# schematic.net
KiCad netlist of a schematic drawn in EAGLE
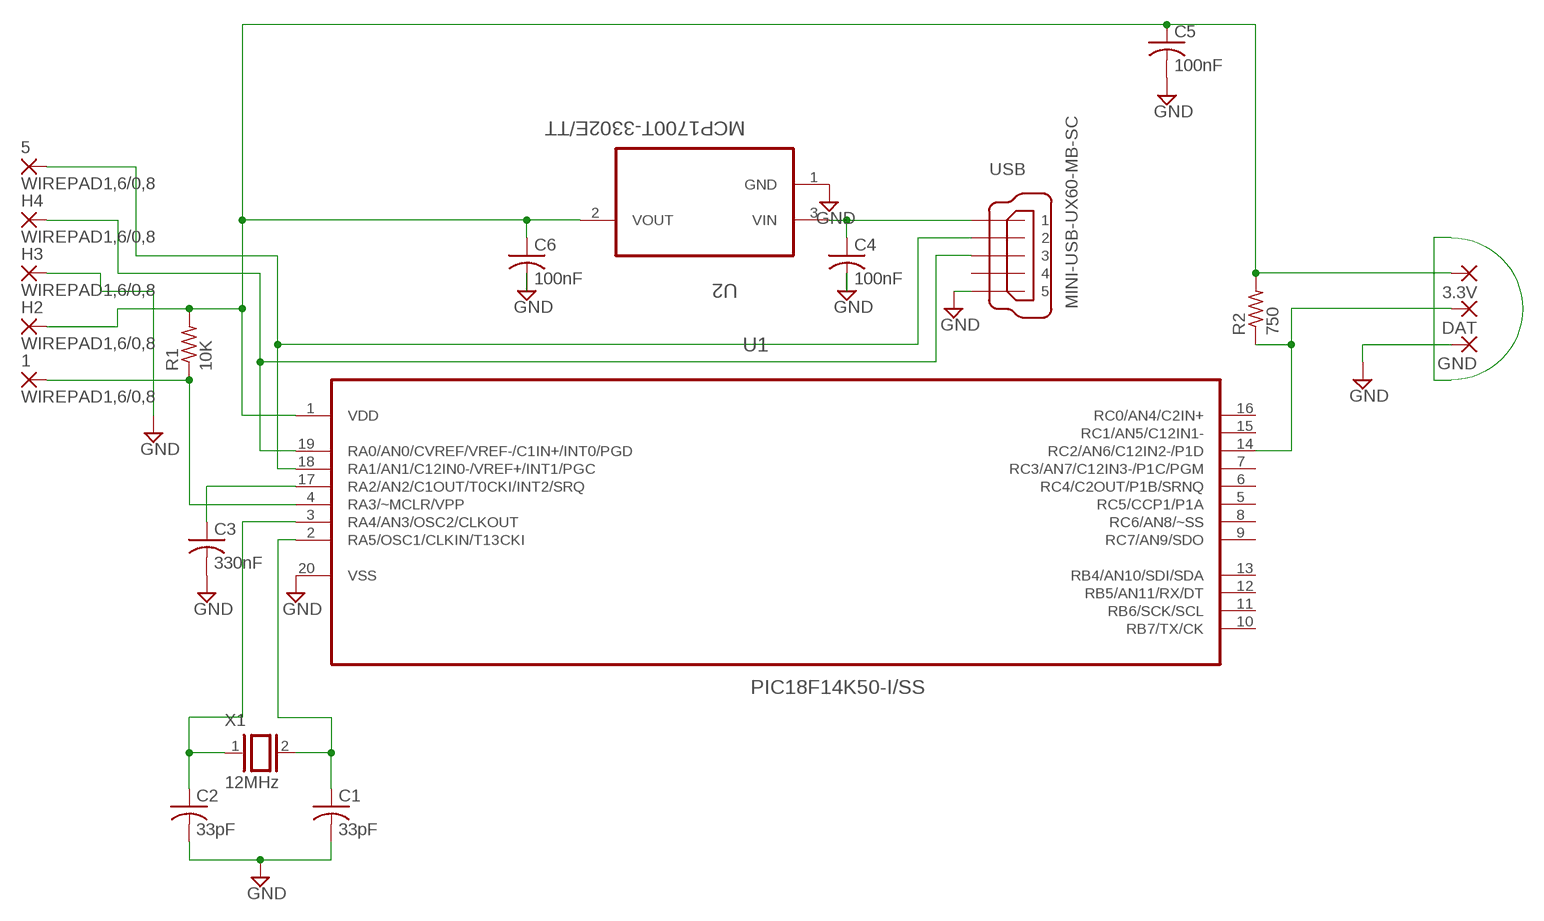
[diagram p0: schematic, sheet 1]

(export (version "E")
  (design (tool "Eeschema 10.0.6"))
  (components
    (comp (ref "1")
      (value "WIREPAD1,6/0,8")
      (footprint "eagle-import:1,6_0,8")
      (libsource (lib "eagle-import") (part "WIREPAD1,6/0,8"))
    )
    (comp (ref "3.3V")
      (value "SMD2")
      (footprint "eagle-import:SMD1,27-2,54")
      (libsource (lib "eagle-import") (part "SMD2"))
    )
    (comp (ref "5")
      (value "WIREPAD1,6/0,8")
      (footprint "eagle-import:1,6_0,8")
      (libsource (lib "eagle-import") (part "WIREPAD1,6/0,8"))
    )
    (comp (ref "C1")
      (value "33pF")
      (footprint "eagle-import:C0402")
      (libsource (lib "eagle-import") (part "C-USC0402"))
    )
    (comp (ref "C2")
      (value "33pF")
      (footprint "eagle-import:C0402")
      (libsource (lib "eagle-import") (part "C-USC0402"))
    )
    (comp (ref "C3")
      (value "330nF")
      (footprint "eagle-import:C0603")
      (libsource (lib "eagle-import") (part "C-USC0603"))
    )
    (comp (ref "C4")
      (value "100nF")
      (footprint "eagle-import:C0402")
      (libsource (lib "eagle-import") (part "C-USC0402"))
    )
    (comp (ref "C5")
      (value "100nF")
      (footprint "eagle-import:C0402")
      (libsource (lib "eagle-import") (part "C-USC0402"))
    )
    (comp (ref "C6")
      (value "100nF")
      (footprint "eagle-import:C0402")
      (libsource (lib "eagle-import") (part "C-USC0402"))
    )
    (comp (ref "DAT")
      (value "SMD2")
      (footprint "eagle-import:SMD1,27-2,54")
      (libsource (lib "eagle-import") (part "SMD2"))
    )
    (comp (ref "GND")
      (value "SMD2")
      (footprint "eagle-import:SMD1,27-2,54")
      (libsource (lib "eagle-import") (part "SMD2"))
    )
    (comp (ref "H2")
      (value "WIREPAD1,6/0,8")
      (footprint "eagle-import:1,6_0,8")
      (libsource (lib "eagle-import") (part "WIREPAD1,6/0,8"))
    )
    (comp (ref "H3")
      (value "WIREPAD1,6/0,8")
      (footprint "eagle-import:1,6_0,8")
      (libsource (lib "eagle-import") (part "WIREPAD1,6/0,8"))
    )
    (comp (ref "H4")
      (value "WIREPAD1,6/0,8")
      (footprint "eagle-import:1,6_0,8")
      (libsource (lib "eagle-import") (part "WIREPAD1,6/0,8"))
    )
    (comp (ref "R1")
      (value "10K")
      (footprint "eagle-import:R0805")
      (libsource (lib "eagle-import") (part "R-US_R0805"))
    )
    (comp (ref "R2")
      (value "750")
      (footprint "eagle-import:R0805")
      (libsource (lib "eagle-import") (part "R-US_R0805"))
    )
    (comp (ref "U1")
      (value "PIC18F14K50-I/SS")
      (footprint "eagle-import:SOP65P780X200-20N")
      (libsource (lib "eagle-import") (part "PIC18F14K50-I/SS"))
    )
    (comp (ref "U2")
      (value "MCP1700T-3302E/TT")
      (footprint "eagle-import:SOT95P237X112-3N")
      (libsource (lib "eagle-import") (part "MCP1700T-3302E/TT"))
    )
    (comp (ref "USB")
      (value "MINI-USB-UX60-MB-SC")
      (footprint "eagle-import:UX60-MB-SC")
      (libsource (lib "eagle-import") (part "MINI-USB-UX60-MB-SC"))
    )
    (comp (ref "X1")
      (value "12MHz")
      (footprint "eagle-import:QS")
      (libsource (lib "eagle-import") (part "XTAL/S"))
    )
  )
  (nets
    (net (code "1") (name "GND") (class "Default")
      (node (ref "C1") (pin "2") (pinfunction "2_2") (pintype "passive"))
      (node (ref "C2") (pin "2") (pinfunction "2_2") (pintype "passive"))
      (node (ref "C3") (pin "2") (pinfunction "2_2") (pintype "passive"))
      (node (ref "C4") (pin "2") (pinfunction "2_2") (pintype "passive"))
      (node (ref "C5") (pin "2") (pinfunction "2_2") (pintype "passive"))
      (node (ref "C6") (pin "2") (pinfunction "2_2") (pintype "passive"))
      (node (ref "GND") (pin "1") (pinfunction "P_1") (pintype "passive"))
      (node (ref "H3") (pin "1") (pinfunction "P_1") (pintype "passive"))
      (node (ref "U1") (pin "20") (pinfunction "VSS_20") (pintype "power_in"))
      (node (ref "U2") (pin "1") (pinfunction "GND_1") (pintype "passive"))
      (node (ref "USB") (pin "P$5") (pinfunction "5_P$5") (pintype "input"))
    )
    (net (code "2") (name "Net-(1-P)") (class "Default")
      (node (ref "1") (pin "1") (pinfunction "P_1") (pintype "passive"))
      (node (ref "R1") (pin "1") (pinfunction "1_1") (pintype "passive"))
      (node (ref "U1") (pin "4") (pinfunction "RA3/~{MCLR/VPP}_4") (pintype "input"))
    )
    (net (code "3") (name "Net-(3.3V-P)") (class "Default")
      (node (ref "3.3V") (pin "1") (pinfunction "P_1") (pintype "passive"))
      (node (ref "C5") (pin "1") (pinfunction "1_1") (pintype "passive"))
      (node (ref "C6") (pin "1") (pinfunction "1_1") (pintype "passive"))
      (node (ref "H2") (pin "1") (pinfunction "P_1") (pintype "passive"))
      (node (ref "R1") (pin "2") (pinfunction "2_2") (pintype "passive"))
      (node (ref "R2") (pin "2") (pinfunction "2_2") (pintype "passive"))
      (node (ref "U1") (pin "1") (pinfunction "VDD_1") (pintype "power_in"))
      (node (ref "U2") (pin "2") (pinfunction "VOUT_2") (pintype "output"))
    )
    (net (code "4") (name "Net-(5-P)") (class "Default")
      (node (ref "5") (pin "1") (pinfunction "P_1") (pintype "passive"))
      (node (ref "U1") (pin "18") (pinfunction "RA1/AN1/C12IN0-/VREF+/INT1/PGC_18") (pintype "bidirectional"))
      (node (ref "USB") (pin "P$2") (pinfunction "2_P$2") (pintype "input"))
    )
    (net (code "5") (name "Net-(DAT-P)") (class "Default")
      (node (ref "DAT") (pin "1") (pinfunction "P_1") (pintype "passive"))
      (node (ref "R2") (pin "1") (pinfunction "1_1") (pintype "passive"))
      (node (ref "U1") (pin "14") (pinfunction "RC2/AN6/C12IN2-/P1D_14") (pintype "bidirectional"))
    )
    (net (code "6") (name "Net-(H4-P)") (class "Default")
      (node (ref "H4") (pin "1") (pinfunction "P_1") (pintype "passive"))
      (node (ref "U1") (pin "19") (pinfunction "RA0/AN0/CVREF/VREF-/C1IN+/INT0/PGD_19") (pintype "bidirectional"))
      (node (ref "USB") (pin "P$3") (pinfunction "3_P$3") (pintype "input"))
    )
    (net (code "7") (name "Net-(U1-RA2{slash}AN2{slash}C1OUT{slash}T0CKI{slash}INT2{slash}SRQ)") (class "Default")
      (node (ref "C3") (pin "1") (pinfunction "1_1") (pintype "passive"))
      (node (ref "U1") (pin "17") (pinfunction "RA2/AN2/C1OUT/T0CKI/INT2/SRQ_17") (pintype "input"))
    )
    (net (code "8") (name "Net-(U1-RA4{slash}AN3{slash}OSC2{slash}CLKOUT)") (class "Default")
      (node (ref "C2") (pin "1") (pinfunction "1_1") (pintype "passive"))
      (node (ref "U1") (pin "3") (pinfunction "RA4/AN3/OSC2/CLKOUT_3") (pintype "bidirectional"))
      (node (ref "X1") (pin "1") (pinfunction "1_1") (pintype "passive"))
    )
    (net (code "9") (name "Net-(U1-RA5{slash}OSC1{slash}CLKIN{slash}T13CKI)") (class "Default")
      (node (ref "C1") (pin "1") (pinfunction "1_1") (pintype "passive"))
      (node (ref "U1") (pin "2") (pinfunction "RA5/OSC1/CLKIN/T13CKI_2") (pintype "bidirectional"))
      (node (ref "X1") (pin "2") (pinfunction "2_2") (pintype "passive"))
    )
    (net (code "10") (name "Net-(U2-VIN)") (class "Default")
      (node (ref "C4") (pin "1") (pinfunction "1_1") (pintype "passive"))
      (node (ref "U2") (pin "3") (pinfunction "VIN_3") (pintype "input"))
      (node (ref "USB") (pin "P$1") (pinfunction "1_P$1") (pintype "input"))
    )
    (net (code "11") (name "unconnected-(U1-RB4{slash}AN10{slash}SDI{slash}SDA-Pad13)") (class "Default")
      (node (ref "U1") (pin "13") (pinfunction "RB4/AN10/SDI/SDA_13") (pintype "bidirectional"))
    )
    (net (code "12") (name "unconnected-(U1-RB5{slash}AN11{slash}RX{slash}DT-Pad12)") (class "Default")
      (node (ref "U1") (pin "12") (pinfunction "RB5/AN11/RX/DT_12") (pintype "bidirectional"))
    )
    (net (code "13") (name "unconnected-(U1-RB6{slash}SCK{slash}SCL-Pad11)") (class "Default")
      (node (ref "U1") (pin "11") (pinfunction "RB6/SCK/SCL_11") (pintype "bidirectional"))
    )
    (net (code "14") (name "unconnected-(U1-RB7{slash}TX{slash}CK-Pad10)") (class "Default")
      (node (ref "U1") (pin "10") (pinfunction "RB7/TX/CK_10") (pintype "bidirectional"))
    )
    (net (code "15") (name "unconnected-(U1-RC0{slash}AN4{slash}C2IN+-Pad16)") (class "Default")
      (node (ref "U1") (pin "16") (pinfunction "RC0/AN4/C2IN+_16") (pintype "bidirectional"))
    )
    (net (code "16") (name "unconnected-(U1-RC1{slash}AN5{slash}C12IN1--Pad15)") (class "Default")
      (node (ref "U1") (pin "15") (pinfunction "RC1/AN5/C12IN1-_15") (pintype "bidirectional"))
    )
    (net (code "17") (name "unconnected-(U1-RC3{slash}AN7{slash}C12IN3-{slash}P1C{slash}PGM-Pad7)") (class "Default")
      (node (ref "U1") (pin "7") (pinfunction "RC3/AN7/C12IN3-/P1C/PGM_7") (pintype "bidirectional"))
    )
    (net (code "18") (name "unconnected-(U1-RC4{slash}C2OUT{slash}P1B{slash}SRNQ-Pad6)") (class "Default")
      (node (ref "U1") (pin "6") (pinfunction "RC4/C2OUT/P1B/SRNQ_6") (pintype "bidirectional"))
    )
    (net (code "19") (name "unconnected-(U1-RC5{slash}CCP1{slash}P1A-Pad5)") (class "Default")
      (node (ref "U1") (pin "5") (pinfunction "RC5/CCP1/P1A_5") (pintype "bidirectional"))
    )
    (net (code "20") (name "unconnected-(U1-RC6{slash}AN8{slash}~{SS}-Pad8)") (class "Default")
      (node (ref "U1") (pin "8") (pinfunction "RC6/AN8/~{SS}_8") (pintype "bidirectional"))
    )
    (net (code "21") (name "unconnected-(U1-RC7{slash}AN9{slash}SDO-Pad9)") (class "Default")
      (node (ref "U1") (pin "9") (pinfunction "RC7/AN9/SDO_9") (pintype "bidirectional"))
    )
    (net (code "22") (name "unconnected-(USB-4-PadP$4)") (class "Default")
      (node (ref "USB") (pin "P$4") (pinfunction "4_P$4") (pintype "input"))
    )
  )
)
